# SK6812.net
KiCad netlist of a schematic drawn in Altium Designer
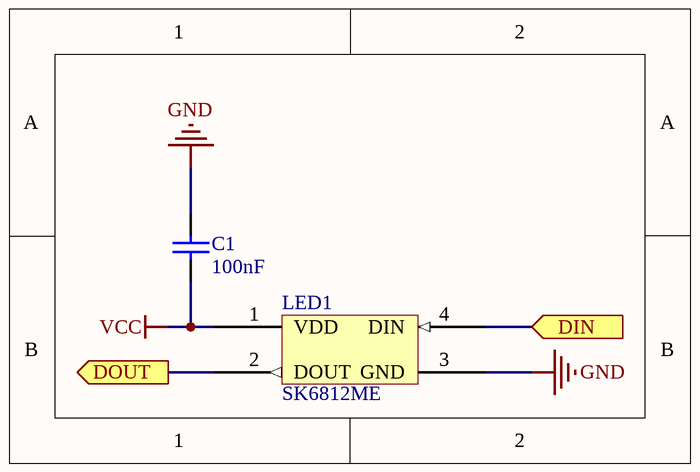
[diagram p0: SK6812.SchDoc]

(export (version "E")
  (design (tool "Eeschema 10.0.6"))
  (components
    (comp (ref "C1")
      (value "100nF")
      (footprint "CAPC1005X55X30LL05T10")
      (fields (field (name "MANUFACTURER") "Kemet") (field (name "PART NUMBER") "C0402C104K4RACTU"))
      (libsource (lib "Altium Content Vault") (part "CAP"))
    )
    (comp (ref "LED1")
      (value "SK6812ME")
      (footprint "SK6812ME")
      (description "Individually Adressable SK6812 Mini-E 3528 LED")
      (libsource (lib "Skayboard") (part "SK6812"))
    )
  )
  (nets
    (net (code "1") (name "/DIN") (class "Default")
      (node (ref "LED1") (pin "4") (pinfunction "DIN_4") (pintype "input"))
    )
    (net (code "2") (name "/DOUT") (class "Default")
      (node (ref "LED1") (pin "2") (pinfunction "DOUT_2") (pintype "output"))
    )
    (net (code "3") (name "GND") (class "Default")
      (node (ref "C1") (pin "2") (pinfunction "2_2") (pintype "passive"))
      (node (ref "LED1") (pin "3") (pinfunction "GND_3") (pintype "power_in"))
    )
    (net (code "4") (name "VCC") (class "Default")
      (node (ref "C1") (pin "1") (pinfunction "1_1") (pintype "passive"))
      (node (ref "LED1") (pin "1") (pinfunction "VDD_1") (pintype "power_in"))
    )
  )
)
